# CAMERA_INTERFACE.net
KiCad netlist of a schematic drawn in Altium Designer
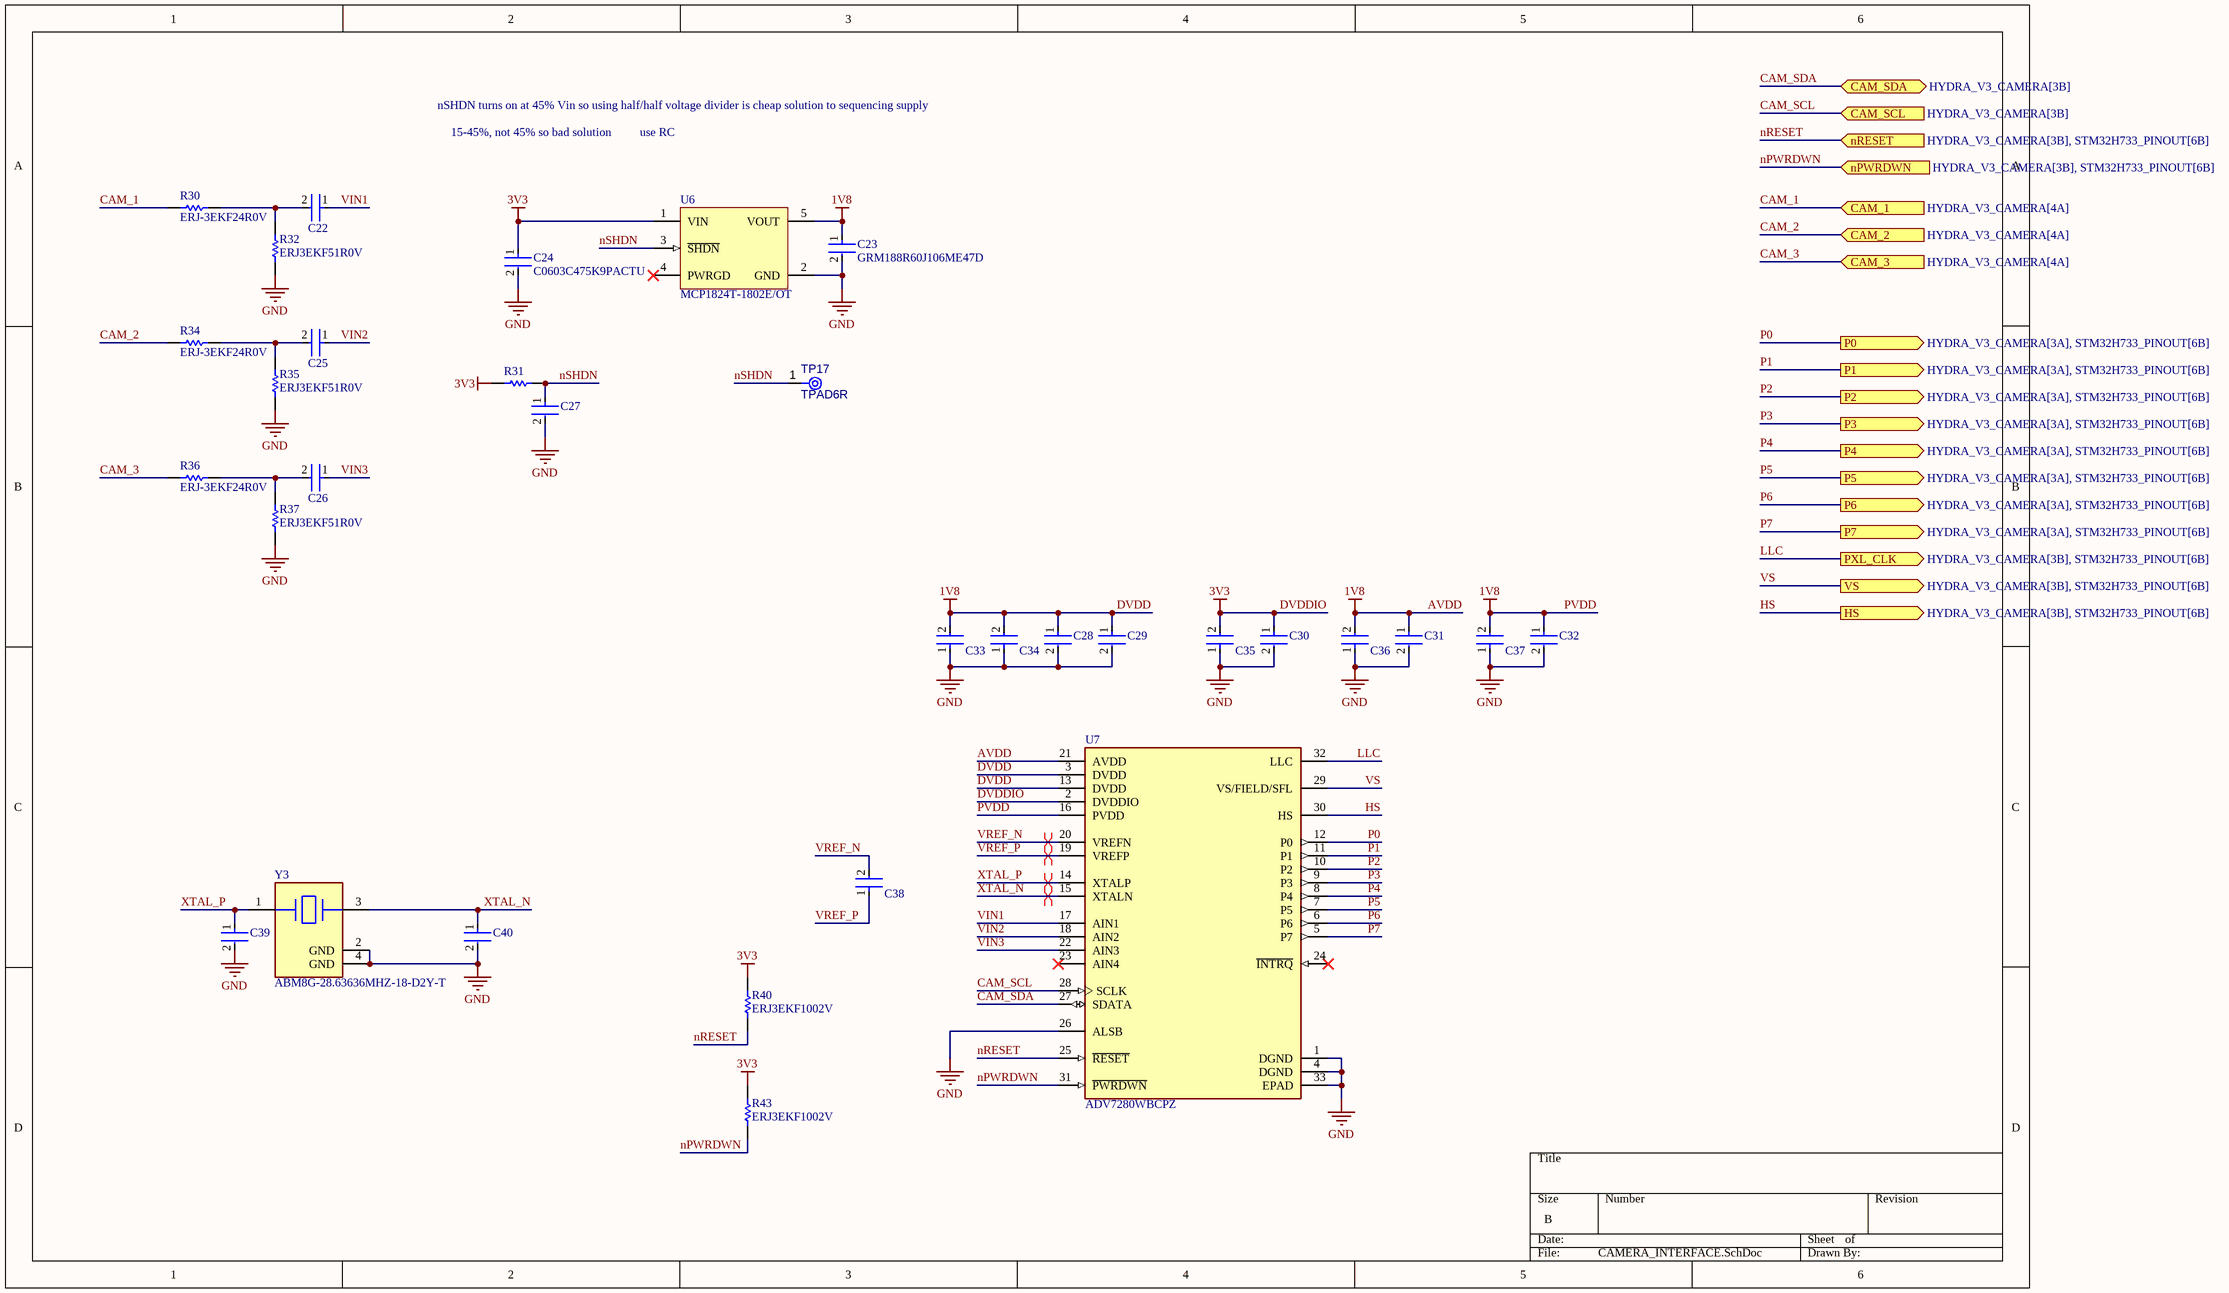
[diagram p0: CAMERA_INTERFACE.SchDoc]

(export (version "E")
  (design (tool "Eeschema 10.0.6"))
  (components
    (comp (ref "C22")
      (value "C0402C104K8PACTU")
      (footprint "FP-C0402-BB-MFG")
      (description "CAP CER 0.1UF 10V X5R 0402")
      (fields (field (name "MANUFACTURER") "Kemet") (field (name "TOLERANCE") "0.1"))
      (libsource (lib "Altium Content Vault") (part "b4654b650e69147ec39a6b967a45e02"))
    )
    (comp (ref "C23")
      (value "GRM188R60J106ME47D")
      (footprint "FP-GRM188-0_1-e0_2_0_55-IPC_A")
      (description "Chip Multilayer Ceramic Capacitors for General Purpose, 0603, 10uF, X5R, 15%, 20%, 6.3V")
      (fields (field (name "VOLTAGE") "6.3V") (field (name "TOLERANCE") "20%"))
      (libsource (lib "Altium Content Vault") (part "02cd4be3c70576c341d710602a673aa"))
    )
    (comp (ref "C24")
      (value "C0603C475K9PACTU")
      (footprint "FP-C0603-CG-MFG")
      (description "CAP CER 4.7UF 6.3V X5R 0603")
      (fields (field (name "TOLERANCE") "10%") (field (name "MANUFACTURER") "Kemet"))
      (libsource (lib "Altium Content Vault") (part "11868f565c42a9108669ba33697ecf6"))
    )
    (comp (ref "C25")
      (value "C0402C104K8PACTU")
      (footprint "FP-C0402-BB-MFG")
      (description "CAP CER 0.1UF 10V X5R 0402")
      (fields (field (name "MANUFACTURER") "Kemet") (field (name "TOLERANCE") "0.1"))
      (libsource (lib "Altium Content Vault") (part "b4654b650e69147ec39a6b967a45e02"))
    )
    (comp (ref "C26")
      (value "C0402C104K8PACTU")
      (footprint "FP-C0402-BB-MFG")
      (description "CAP CER 0.1UF 10V X5R 0402")
      (fields (field (name "MANUFACTURER") "Kemet") (field (name "TOLERANCE") "0.1"))
      (libsource (lib "Altium Content Vault") (part "b4654b650e69147ec39a6b967a45e02"))
    )
    (comp (ref "C27")
      (value "C0603C475K9PACTU")
      (footprint "FP-C0603-CG-MFG")
      (description "CAP CER 4.7UF 6.3V X5R 0603")
      (fields (field (name "TOLERANCE") "10%") (field (name "MANUFACTURER") "Kemet"))
      (libsource (lib "Altium Content Vault") (part "11868f565c42a9108669ba33697ecf6"))
    )
    (comp (ref "C28")
      (value "CC0603KRX7R9BB103")
      (footprint "FP-CC0603-DA-MFG")
      (description "CAP CER 10000PF 50V X7R 0603")
      (fields (field (name "TOLERANCE") "0.1") (field (name "MANUFACTURER") "YAGEO"))
      (libsource (lib "Altium Content Vault") (part "11868f565c42a9108669ba33697ecf6"))
    )
    (comp (ref "C29")
      (value "CC0603KRX7R9BB103")
      (footprint "FP-CC0603-DA-MFG")
      (description "CAP CER 10000PF 50V X7R 0603")
      (fields (field (name "TOLERANCE") "0.1") (field (name "MANUFACTURER") "YAGEO"))
      (libsource (lib "Altium Content Vault") (part "11868f565c42a9108669ba33697ecf6"))
    )
    (comp (ref "C30")
      (value "CC0603KRX7R9BB103")
      (footprint "FP-CC0603-DA-MFG")
      (description "CAP CER 10000PF 50V X7R 0603")
      (fields (field (name "TOLERANCE") "0.1") (field (name "MANUFACTURER") "YAGEO"))
      (libsource (lib "Altium Content Vault") (part "11868f565c42a9108669ba33697ecf6"))
    )
    (comp (ref "C31")
      (value "CC0603KRX7R9BB103")
      (footprint "FP-CC0603-DA-MFG")
      (description "CAP CER 10000PF 50V X7R 0603")
      (fields (field (name "TOLERANCE") "0.1") (field (name "MANUFACTURER") "YAGEO"))
      (libsource (lib "Altium Content Vault") (part "11868f565c42a9108669ba33697ecf6"))
    )
    (comp (ref "C32")
      (value "CC0603KRX7R9BB103")
      (footprint "FP-CC0603-DA-MFG")
      (description "CAP CER 10000PF 50V X7R 0603")
      (fields (field (name "TOLERANCE") "0.1") (field (name "MANUFACTURER") "YAGEO"))
      (libsource (lib "Altium Content Vault") (part "11868f565c42a9108669ba33697ecf6"))
    )
    (comp (ref "C33")
      (value "C0402C104K8PACTU")
      (footprint "FP-C0402-BB-MFG")
      (description "CAP CER 0.1UF 10V X5R 0402")
      (fields (field (name "MANUFACTURER") "Kemet") (field (name "TOLERANCE") "0.1"))
      (libsource (lib "Altium Content Vault") (part "b4654b650e69147ec39a6b967a45e02"))
    )
    (comp (ref "C34")
      (value "C0402C104K8PACTU")
      (footprint "FP-C0402-BB-MFG")
      (description "CAP CER 0.1UF 10V X5R 0402")
      (fields (field (name "MANUFACTURER") "Kemet") (field (name "TOLERANCE") "0.1"))
      (libsource (lib "Altium Content Vault") (part "b4654b650e69147ec39a6b967a45e02"))
    )
    (comp (ref "C35")
      (value "C0402C104K8PACTU")
      (footprint "FP-C0402-BB-MFG")
      (description "CAP CER 0.1UF 10V X5R 0402")
      (fields (field (name "MANUFACTURER") "Kemet") (field (name "TOLERANCE") "0.1"))
      (libsource (lib "Altium Content Vault") (part "b4654b650e69147ec39a6b967a45e02"))
    )
    (comp (ref "C36")
      (value "C0402C104K8PACTU")
      (footprint "FP-C0402-BB-MFG")
      (description "CAP CER 0.1UF 10V X5R 0402")
      (fields (field (name "MANUFACTURER") "Kemet") (field (name "TOLERANCE") "0.1"))
      (libsource (lib "Altium Content Vault") (part "b4654b650e69147ec39a6b967a45e02"))
    )
    (comp (ref "C37")
      (value "C0402C104K8PACTU")
      (footprint "FP-C0402-BB-MFG")
      (description "CAP CER 0.1UF 10V X5R 0402")
      (fields (field (name "MANUFACTURER") "Kemet") (field (name "TOLERANCE") "0.1"))
      (libsource (lib "Altium Content Vault") (part "b4654b650e69147ec39a6b967a45e02"))
    )
    (comp (ref "C38")
      (value "C0402C104K8PACTU")
      (footprint "FP-C0402-BB-MFG")
      (description "CAP CER 0.1UF 10V X5R 0402")
      (fields (field (name "MANUFACTURER") "Kemet") (field (name "TOLERANCE") "0.1"))
      (libsource (lib "Altium Content Vault") (part "b4654b650e69147ec39a6b967a45e02"))
    )
    (comp (ref "C39")
      (value "C0603C470J1GACTU")
      (footprint "FP-C0603C-CF-MFG")
      (description "CAP CER 47PF 100V 5% NP0 0603")
      (fields
        (field (name "MANUFACTURER") "KEMET")
        (field (name "OCTOPART") "https://octopart.com/c0603c470j1gactu-kemet-3768219")
      )
      (libsource (lib "Altium Content Vault") (part "b4654b650e69147ec39a6b967a45e02"))
    )
    (comp (ref "C40")
      (value "C0603C470J1GACTU")
      (footprint "FP-C0603C-CF-MFG")
      (description "CAP CER 47PF 100V 5% NP0 0603")
      (fields
        (field (name "MANUFACTURER") "KEMET")
        (field (name "OCTOPART") "https://octopart.com/c0603c470j1gactu-kemet-3768219")
      )
      (libsource (lib "Altium Content Vault") (part "b4654b650e69147ec39a6b967a45e02"))
    )
    (comp (ref "R30")
      (value "ERJ-3EKF24R0V")
      (footprint "RESC1608X55X30ML15T15")
      (fields (field (name "MANUFACTURER") "Panasonic"))
      (libsource (lib "Altium Content Vault") (part "RES"))
    )
    (comp (ref "R31")
      (value "ERJ3EKF1002V")
      (footprint "RESC1609X55X30LL15T15")
      (description "Chip Resistor, 10 KOhm, +/- 1%, 0.1 W, -55 to 155 degC, 0603 (1608 Metric), RoHS, Tape and Reel")
      (fields (field (name "TOLERANCE") "1%") (field (name "MANUFACTURER") "Panasonic"))
      (libsource (lib "Altium Content Vault") (part "RES-2"))
    )
    (comp (ref "R32")
      (value "ERJ3EKF51R0V")
      (footprint "RESC1608X55X30NL15T15")
      (fields (field (name "MANUFACTURER") "Panasonic"))
      (libsource (lib "Altium Content Vault") (part "RES"))
    )
    (comp (ref "R34")
      (value "ERJ-3EKF24R0V")
      (footprint "RESC1608X55X30ML15T15")
      (fields (field (name "MANUFACTURER") "Panasonic"))
      (libsource (lib "Altium Content Vault") (part "RES"))
    )
    (comp (ref "R35")
      (value "ERJ3EKF51R0V")
      (footprint "RESC1608X55X30NL15T15")
      (fields (field (name "MANUFACTURER") "Panasonic"))
      (libsource (lib "Altium Content Vault") (part "RES"))
    )
    (comp (ref "R36")
      (value "ERJ-3EKF24R0V")
      (footprint "RESC1608X55X30ML15T15")
      (fields (field (name "MANUFACTURER") "Panasonic"))
      (libsource (lib "Altium Content Vault") (part "RES"))
    )
    (comp (ref "R37")
      (value "ERJ3EKF51R0V")
      (footprint "RESC1608X55X30NL15T15")
      (fields (field (name "MANUFACTURER") "Panasonic"))
      (libsource (lib "Altium Content Vault") (part "RES"))
    )
    (comp (ref "R40")
      (value "ERJ3EKF1002V")
      (footprint "RESC1609X55X30LL15T15")
      (description "Chip Resistor, 10 KOhm, +/- 1%, 0.1 W, -55 to 155 degC, 0603 (1608 Metric), RoHS, Tape and Reel")
      (fields (field (name "TOLERANCE") "1%") (field (name "MANUFACTURER") "Panasonic"))
      (libsource (lib "Altium Content Vault") (part "RES-2"))
    )
    (comp (ref "R43")
      (value "ERJ3EKF1002V")
      (footprint "RESC1609X55X30LL15T15")
      (description "Chip Resistor, 10 KOhm, +/- 1%, 0.1 W, -55 to 155 degC, 0603 (1608 Metric), RoHS, Tape and Reel")
      (fields (field (name "TOLERANCE") "1%") (field (name "MANUFACTURER") "Panasonic"))
      (libsource (lib "Altium Content Vault") (part "RES-2"))
    )
    (comp (ref "TP17")
      (value "TPAD6R")
      (footprint "TP06R")
      (description "0.6mm round")
      (libsource (lib "uORocketry Hardware") (part "CMP-001-0001-4"))
    )
    (comp (ref "U6")
      (value "MCP1824T-1802E/OT")
      (footprint "SOT-23-OT5_M")
      (libsource (lib "Altium Content Vault") (part "PM-LINEREG-MCP1824-IL5B"))
    )
    (comp (ref "U7")
      (value "ADV7280WBCPZ")
      (footprint "FP-CP-32-12-MFG")
      (description "IC VIDEO DECODER SDTV 32-LFCSP")
      (libsource (lib "Altium Content Vault") (part "2e15c7328653806e765036f9cdadbb7"))
    )
    (comp (ref "Y3")
      (value "ABM8G-28.63636MHZ-18-D2Y-T")
      (footprint "FP-ABM8G-MFG")
      (description "Crystal 28.63636MHz ±20ppm (Tol) ±30ppm (Stability) 18pF FUND 50Ω 4-Pin SMD T/R")
      (fields (field (name "TOLERANCE") "20ppm"))
      (libsource (lib "Altium Content Vault") (part "48e526d86b7f2615d98721063c72f49"))
    )
  )
  (nets
    (net (code "1") (name "/CAM_1") (class "Default")
      (node (ref "R30") (pin "1") (pinfunction "1_1") (pintype "passive"))
    )
    (net (code "2") (name "/CAM_2") (class "Default")
      (node (ref "R34") (pin "1") (pinfunction "1_1") (pintype "passive"))
    )
    (net (code "3") (name "/CAM_3") (class "Default")
      (node (ref "R36") (pin "1") (pinfunction "1_1") (pintype "passive"))
    )
    (net (code "4") (name "/CAM_SCL") (class "Default")
      (node (ref "U7") (pin "28") (pinfunction "SCLK_28") (pintype "input"))
    )
    (net (code "5") (name "/CAM_SDA") (class "Default")
      (node (ref "U7") (pin "27") (pinfunction "SDATA_27") (pintype "bidirectional"))
    )
    (net (code "6") (name "/HS") (class "Default")
      (node (ref "U7") (pin "30") (pinfunction "HS_30") (pintype "passive"))
    )
    (net (code "7") (name "/LLC") (class "Default")
      (node (ref "U7") (pin "32") (pinfunction "LLC_32") (pintype "passive"))
    )
    (net (code "8") (name "/P0") (class "Default")
      (node (ref "U7") (pin "12") (pinfunction "P0_12") (pintype "output"))
    )
    (net (code "9") (name "/P1") (class "Default")
      (node (ref "U7") (pin "11") (pinfunction "P1_11") (pintype "output"))
    )
    (net (code "10") (name "/P2") (class "Default")
      (node (ref "U7") (pin "10") (pinfunction "P2_10") (pintype "output"))
    )
    (net (code "11") (name "/P3") (class "Default")
      (node (ref "U7") (pin "9") (pinfunction "P3_9") (pintype "output"))
    )
    (net (code "12") (name "/P4") (class "Default")
      (node (ref "U7") (pin "8") (pinfunction "P4_8") (pintype "output"))
    )
    (net (code "13") (name "/P5") (class "Default")
      (node (ref "U7") (pin "7") (pinfunction "P5_7") (pintype "output"))
    )
    (net (code "14") (name "/P6") (class "Default")
      (node (ref "U7") (pin "6") (pinfunction "P6_6") (pintype "output"))
    )
    (net (code "15") (name "/P7") (class "Default")
      (node (ref "U7") (pin "5") (pinfunction "P7_5") (pintype "output"))
    )
    (net (code "16") (name "/VIN1") (class "Default")
      (node (ref "C22") (pin "1") (pinfunction "1_1") (pintype "passive"))
      (node (ref "U7") (pin "17") (pinfunction "AIN1_17") (pintype "tri_state"))
    )
    (net (code "17") (name "/VIN2") (class "Default")
      (node (ref "C25") (pin "1") (pinfunction "1_1") (pintype "passive"))
      (node (ref "U7") (pin "18") (pinfunction "AIN2_18") (pintype "tri_state"))
    )
    (net (code "18") (name "/VIN3") (class "Default")
      (node (ref "C26") (pin "1") (pinfunction "1_1") (pintype "passive"))
      (node (ref "U7") (pin "22") (pinfunction "AIN3_22") (pintype "passive"))
    )
    (net (code "19") (name "/VREF_N") (class "Default")
      (node (ref "C38") (pin "2") (pinfunction "2_2") (pintype "passive"))
      (node (ref "U7") (pin "20") (pinfunction "VREFN_20") (pintype "passive"))
    )
    (net (code "20") (name "/VREF_P") (class "Default")
      (node (ref "C38") (pin "1") (pinfunction "1_1") (pintype "passive"))
      (node (ref "U7") (pin "19") (pinfunction "VREFP_19") (pintype "passive"))
    )
    (net (code "21") (name "/VS") (class "Default")
      (node (ref "U7") (pin "29") (pinfunction "VS/FIELD/SFL_29") (pintype "passive"))
    )
    (net (code "22") (name "/XTAL_N") (class "Default")
      (node (ref "C40") (pin "1") (pinfunction "1_1") (pintype "passive"))
      (node (ref "U7") (pin "15") (pinfunction "XTALN_15") (pintype "passive"))
      (node (ref "Y3") (pin "3") (pinfunction "3_3") (pintype "passive"))
    )
    (net (code "23") (name "/XTAL_P") (class "Default")
      (node (ref "C39") (pin "1") (pinfunction "1_1") (pintype "passive"))
      (node (ref "U7") (pin "14") (pinfunction "XTALP_14") (pintype "passive"))
      (node (ref "Y3") (pin "1") (pinfunction "1_1") (pintype "passive"))
    )
    (net (code "24") (name "/nPWRDWN") (class "Default")
      (node (ref "R43") (pin "1") (pinfunction "1_1") (pintype "passive"))
      (node (ref "U7") (pin "31") (pinfunction "~{PWRDWN}_31") (pintype "input"))
    )
    (net (code "25") (name "/nRESET") (class "Default")
      (node (ref "R40") (pin "1") (pinfunction "1_1") (pintype "passive"))
      (node (ref "U7") (pin "25") (pinfunction "~{RESET}_25") (pintype "input"))
    )
    (net (code "26") (name "/nSHDN") (class "Default")
      (node (ref "C27") (pin "1") (pinfunction "1_1") (pintype "passive"))
      (node (ref "R31") (pin "2") (pinfunction "2_2") (pintype "passive"))
      (node (ref "TP17") (pin "1") (pinfunction "TP_1") (pintype "passive"))
      (node (ref "U6") (pin "3") (pinfunction "~{SHDN}_3") (pintype "input"))
    )
    (net (code "27") (name "1V8") (class "Default")
      (node (ref "C23") (pin "1") (pinfunction "1_1") (pintype "passive"))
      (node (ref "C28") (pin "1") (pinfunction "1_1") (pintype "passive"))
      (node (ref "C29") (pin "1") (pinfunction "1_1") (pintype "passive"))
      (node (ref "C31") (pin "1") (pinfunction "1_1") (pintype "passive"))
      (node (ref "C32") (pin "1") (pinfunction "1_1") (pintype "passive"))
      (node (ref "C33") (pin "2") (pinfunction "2_2") (pintype "passive"))
      (node (ref "C34") (pin "2") (pinfunction "2_2") (pintype "passive"))
      (node (ref "C36") (pin "2") (pinfunction "2_2") (pintype "passive"))
      (node (ref "C37") (pin "2") (pinfunction "2_2") (pintype "passive"))
      (node (ref "U6") (pin "5") (pinfunction "VOUT_5") (pintype "power_in"))
      (node (ref "U7") (pin "13") (pinfunction "DVDD_13") (pintype "power_in"))
      (node (ref "U7") (pin "16") (pinfunction "PVDD_16") (pintype "power_in"))
      (node (ref "U7") (pin "21") (pinfunction "AVDD_21") (pintype "power_in"))
      (node (ref "U7") (pin "3") (pinfunction "DVDD_3") (pintype "power_in"))
    )
    (net (code "28") (name "3V3") (class "Default")
      (node (ref "C24") (pin "1") (pinfunction "1_1") (pintype "passive"))
      (node (ref "C30") (pin "1") (pinfunction "1_1") (pintype "passive"))
      (node (ref "C35") (pin "2") (pinfunction "2_2") (pintype "passive"))
      (node (ref "R31") (pin "1") (pinfunction "1_1") (pintype "passive"))
      (node (ref "R40") (pin "2") (pinfunction "2_2") (pintype "passive"))
      (node (ref "R43") (pin "2") (pinfunction "2_2") (pintype "passive"))
      (node (ref "U6") (pin "1") (pinfunction "VIN_1") (pintype "power_in"))
      (node (ref "U7") (pin "2") (pinfunction "DVDDIO_2") (pintype "power_in"))
    )
    (net (code "29") (name "GND") (class "Default")
      (node (ref "C23") (pin "2") (pinfunction "2_2") (pintype "passive"))
      (node (ref "C24") (pin "2") (pinfunction "2_2") (pintype "passive"))
      (node (ref "C27") (pin "2") (pinfunction "2_2") (pintype "passive"))
      (node (ref "C28") (pin "2") (pinfunction "2_2") (pintype "passive"))
      (node (ref "C29") (pin "2") (pinfunction "2_2") (pintype "passive"))
      (node (ref "C30") (pin "2") (pinfunction "2_2") (pintype "passive"))
      (node (ref "C31") (pin "2") (pinfunction "2_2") (pintype "passive"))
      (node (ref "C32") (pin "2") (pinfunction "2_2") (pintype "passive"))
      (node (ref "C33") (pin "1") (pinfunction "1_1") (pintype "passive"))
      (node (ref "C34") (pin "1") (pinfunction "1_1") (pintype "passive"))
      (node (ref "C35") (pin "1") (pinfunction "1_1") (pintype "passive"))
      (node (ref "C36") (pin "1") (pinfunction "1_1") (pintype "passive"))
      (node (ref "C37") (pin "1") (pinfunction "1_1") (pintype "passive"))
      (node (ref "C39") (pin "2") (pinfunction "2_2") (pintype "passive"))
      (node (ref "C40") (pin "2") (pinfunction "2_2") (pintype "passive"))
      (node (ref "R32") (pin "1") (pinfunction "1_1") (pintype "passive"))
      (node (ref "R35") (pin "1") (pinfunction "1_1") (pintype "passive"))
      (node (ref "R37") (pin "1") (pinfunction "1_1") (pintype "passive"))
      (node (ref "U6") (pin "2") (pinfunction "GND_2") (pintype "power_in"))
      (node (ref "U7") (pin "1") (pinfunction "DGND_1") (pintype "power_in"))
      (node (ref "U7") (pin "26") (pinfunction "ALSB_26") (pintype "passive"))
      (node (ref "U7") (pin "33") (pinfunction "EPAD_33") (pintype "passive"))
      (node (ref "U7") (pin "4") (pinfunction "DGND_4") (pintype "power_in"))
      (node (ref "Y3") (pin "2") (pinfunction "GND_2") (pintype "power_in"))
      (node (ref "Y3") (pin "4") (pinfunction "GND_4") (pintype "power_in"))
    )
    (net (code "30") (name "Net-(C22-Pad2)") (class "Default")
      (node (ref "C22") (pin "2") (pinfunction "2_2") (pintype "passive"))
      (node (ref "R30") (pin "2") (pinfunction "2_2") (pintype "passive"))
      (node (ref "R32") (pin "2") (pinfunction "2_2") (pintype "passive"))
    )
    (net (code "31") (name "Net-(C25-Pad2)") (class "Default")
      (node (ref "C25") (pin "2") (pinfunction "2_2") (pintype "passive"))
      (node (ref "R34") (pin "2") (pinfunction "2_2") (pintype "passive"))
      (node (ref "R35") (pin "2") (pinfunction "2_2") (pintype "passive"))
    )
    (net (code "32") (name "Net-(C26-Pad2)") (class "Default")
      (node (ref "C26") (pin "2") (pinfunction "2_2") (pintype "passive"))
      (node (ref "R36") (pin "2") (pinfunction "2_2") (pintype "passive"))
      (node (ref "R37") (pin "2") (pinfunction "2_2") (pintype "passive"))
    )
    (net (code "33") (name "unconnected-(U6-PWRGD-Pad4)") (class "Default")
      (node (ref "U6") (pin "4") (pinfunction "PWRGD_4") (pintype "power_in+no_connect"))
    )
    (net (code "34") (name "unconnected-(U7-AIN4-Pad23)") (class "Default")
      (node (ref "U7") (pin "23") (pinfunction "AIN4_23") (pintype "passive+no_connect"))
    )
    (net (code "35") (name "unconnected-(U7-~{INTRQ}-Pad24)") (class "Default")
      (node (ref "U7") (pin "24") (pinfunction "~{INTRQ}_24") (pintype "input+no_connect"))
    )
  )
)
